# Step-down_converter.net
KiCad netlist of a schematic drawn in Altium Designer
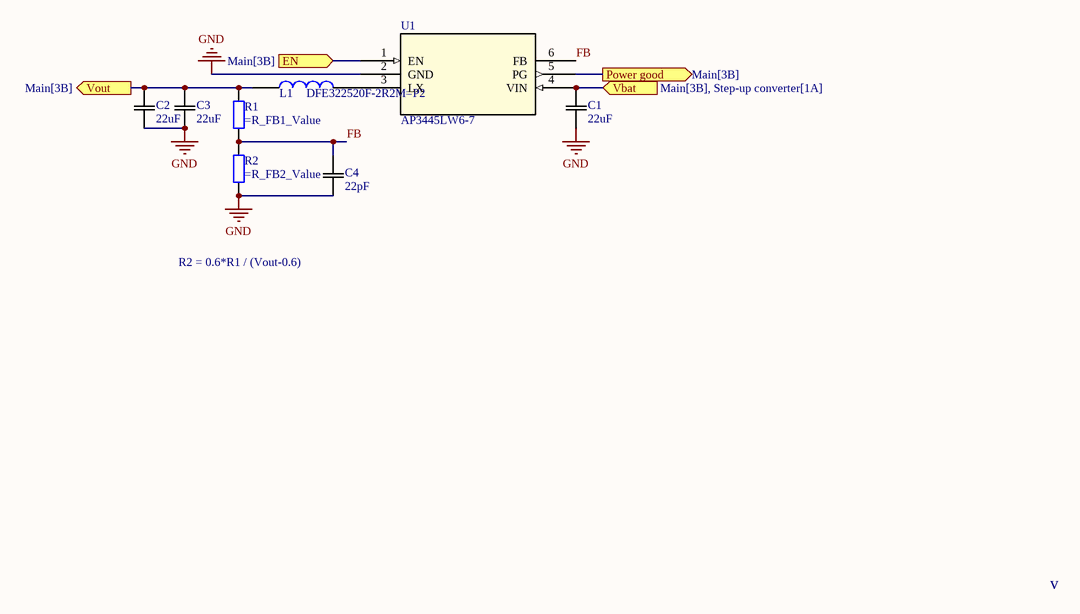
[diagram p0: Step-down converter.SchDoc]

(export (version "E")
  (design (tool "Eeschema 10.0.6"))
  (components
    (comp (ref "C1")
      (value "22uF")
      (footprint "CAPC2012X94N")
      (description "No Description Available")
      (libsource (lib "General Components") (part "CAP 0805"))
    )
    (comp (ref "C2")
      (value "22uF")
      (footprint "CAPC2012X94N")
      (description "No Description Available")
      (libsource (lib "General Components") (part "CAP 0805"))
    )
    (comp (ref "C3")
      (value "22uF")
      (footprint "CAPC2012X94N")
      (description "No Description Available")
      (libsource (lib "General Components") (part "CAP 0805"))
    )
    (comp (ref "C4")
      (value "22pF")
      (footprint "CAPC2012X94N")
      (description "No Description Available")
      (libsource (lib "General Components") (part "CAP 0805"))
    )
    (comp (ref "L1")
      (value "DFE322520F-2R2M=P2")
      (footprint "INDC3225X200N")
      (description "2.2 H Shielded Wirewound Inductor 3.3 A 40mOhm Max 1210 (3225 Metric)")
      (libsource (lib "DFE322520F-2R2M=P2") (part "DFE322520F-2R2M=P2"))
    )
    (comp (ref "R1")
      (value "~")
      (footprint "0805")
      (description "Resistor")
      (libsource (lib "General Components") (part "Res 0805"))
    )
    (comp (ref "R2")
      (value "~")
      (footprint "0805")
      (description "Resistor")
      (libsource (lib "General Components") (part "Res 0805"))
    )
    (comp (ref "U1")
      (value "AP3445LW6-7")
      (footprint "SOT26_AP3445_DIO")
      (description "No Description Available")
      (fields (field (name "COPYRIGHT") "Copyright (C) 2024 Ultra Librarian. All rights reserved."))
      (libsource (lib "AP3445LW6-7") (part "AP3445LW6-7"))
    )
  )
  (nets
    (net (code "1") (name "/EN") (class "Default")
      (node (ref "U1") (pin "1") (pinfunction "EN_1") (pintype "input"))
    )
    (net (code "2") (name "/FB") (class "Default")
      (node (ref "C4") (pin "2") (pinfunction "12_2") (pintype "passive"))
      (node (ref "R1") (pin "1") (pinfunction "1_1") (pintype "passive"))
      (node (ref "R2") (pin "2") (pinfunction "2_2") (pintype "passive"))
      (node (ref "U1") (pin "6") (pinfunction "FB_6") (pintype "passive"))
    )
    (net (code "3") (name "/Power good") (class "Default")
      (node (ref "U1") (pin "5") (pinfunction "PG_5") (pintype "output"))
    )
    (net (code "4") (name "/Vbat") (class "Default")
      (node (ref "C1") (pin "2") (pinfunction "12_2") (pintype "passive"))
      (node (ref "U1") (pin "4") (pinfunction "VIN_4") (pintype "input"))
    )
    (net (code "5") (name "/Vout") (class "Default")
      (node (ref "C2") (pin "2") (pinfunction "12_2") (pintype "passive"))
      (node (ref "C3") (pin "2") (pinfunction "12_2") (pintype "passive"))
      (node (ref "L1") (pin "1") (pinfunction "1_1") (pintype "passive"))
      (node (ref "R1") (pin "2") (pinfunction "2_2") (pintype "passive"))
    )
    (net (code "6") (name "GND") (class "Default")
      (node (ref "C1") (pin "1") (pinfunction "11_1") (pintype "passive"))
      (node (ref "C2") (pin "1") (pinfunction "11_1") (pintype "passive"))
      (node (ref "C3") (pin "1") (pinfunction "11_1") (pintype "passive"))
      (node (ref "C4") (pin "1") (pinfunction "11_1") (pintype "passive"))
      (node (ref "R2") (pin "1") (pinfunction "1_1") (pintype "passive"))
      (node (ref "U1") (pin "2") (pinfunction "GND_2") (pintype "power_in"))
    )
    (net (code "7") (name "Net-(U1-LX)") (class "Default")
      (node (ref "L1") (pin "2") (pinfunction "2_2") (pintype "passive"))
      (node (ref "U1") (pin "3") (pinfunction "LX_3") (pintype "passive"))
    )
  )
)
